# schema.net
KiCad netlist of a schematic drawn in EAGLE
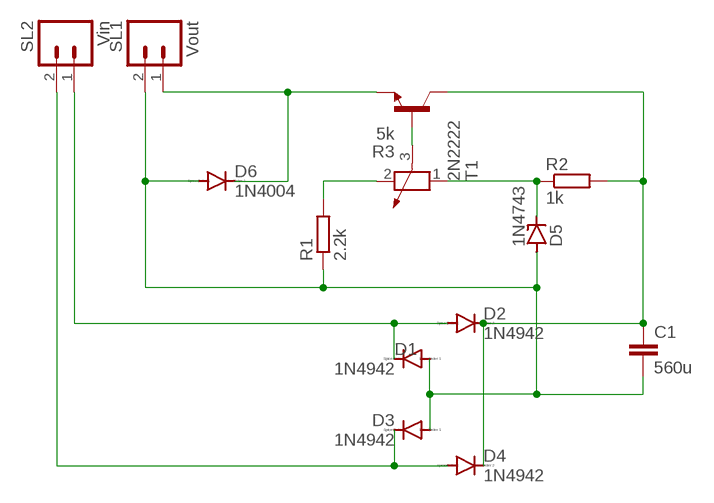
[diagram p0: schematic, sheet 1]

(export (version "E")
  (design (tool "Eeschema 10.0.6"))
  (components
    (comp (ref "C1")
      (value "560u")
      (footprint "eagle-import:C025-025X050")
      (libsource (lib "eagle-import") (part "C-EU025-025X050"))
    )
    (comp (ref "D1")
      (value "1N4942")
      (footprint "eagle-import:DO41-10")
      (libsource (lib "eagle-import") (part "1N4942"))
    )
    (comp (ref "D2")
      (value "1N4942")
      (footprint "eagle-import:DO41-10")
      (libsource (lib "eagle-import") (part "1N4942"))
    )
    (comp (ref "D3")
      (value "1N4942")
      (footprint "eagle-import:DO41-10")
      (libsource (lib "eagle-import") (part "1N4942"))
    )
    (comp (ref "D4")
      (value "1N4942")
      (footprint "eagle-import:DO41-10")
      (libsource (lib "eagle-import") (part "1N4942"))
    )
    (comp (ref "D5")
      (value "1N4743")
      (footprint "eagle-import:DO41Z10")
      (libsource (lib "eagle-import") (part "1N4728"))
    )
    (comp (ref "D6")
      (value "1N4004")
      (footprint "eagle-import:DO41-10")
      (libsource (lib "eagle-import") (part "1N4004"))
    )
    (comp (ref "R1")
      (value "2.2k")
      (footprint "eagle-import:0204_7")
      (libsource (lib "eagle-import") (part "R-EU_0204/7"))
    )
    (comp (ref "R2")
      (value "1k")
      (footprint "eagle-import:0204_7")
      (libsource (lib "eagle-import") (part "R-EU_0204/7"))
    )
    (comp (ref "R3")
      (value "5k")
      (footprint "eagle-import:PT-10")
      (libsource (lib "eagle-import") (part "POTENTIOMETER_PT-10"))
    )
    (comp (ref "SL1")
      (value "Vout")
      (footprint "eagle-import:02P")
      (libsource (lib "eagle-import") (part "M02"))
    )
    (comp (ref "SL2")
      (value "Vin")
      (footprint "eagle-import:02P")
      (libsource (lib "eagle-import") (part "M02"))
    )
    (comp (ref "T1")
      (value "2N2222")
      (footprint "eagle-import:TO18")
      (libsource (lib "eagle-import") (part "2N2222"))
    )
  )
  (nets
    (net (code "1") (name "Net-(C1-Pad2)") (class "Default")
      (node (ref "C1") (pin "2") (pinfunction "2_2") (pintype "passive"))
      (node (ref "D1") (pin "A") (pinfunction "A_A") (pintype "passive"))
      (node (ref "D3") (pin "A") (pinfunction "A_A") (pintype "passive"))
      (node (ref "D5") (pin "A") (pinfunction "A_A") (pintype "passive"))
      (node (ref "D6") (pin "A") (pinfunction "A_A") (pintype "passive"))
      (node (ref "R1") (pin "1") (pinfunction "1_1") (pintype "passive"))
      (node (ref "SL1") (pin "2") (pinfunction "2_2") (pintype "passive"))
    )
    (net (code "2") (name "Net-(D1-PadC)") (class "Default")
      (node (ref "D1") (pin "C") (pinfunction "C_C") (pintype "passive"))
      (node (ref "D2") (pin "A") (pinfunction "A_A") (pintype "passive"))
      (node (ref "SL2") (pin "1") (pinfunction "1_1") (pintype "passive"))
    )
    (net (code "3") (name "Net-(D3-PadC)") (class "Default")
      (node (ref "D3") (pin "C") (pinfunction "C_C") (pintype "passive"))
      (node (ref "D4") (pin "A") (pinfunction "A_A") (pintype "passive"))
      (node (ref "SL2") (pin "2") (pinfunction "2_2") (pintype "passive"))
    )
    (net (code "4") (name "Net-(D5-PadC)") (class "Default")
      (node (ref "D5") (pin "C") (pinfunction "C_C") (pintype "passive"))
      (node (ref "R2") (pin "1") (pinfunction "1_1") (pintype "passive"))
      (node (ref "R3") (pin "1") (pinfunction "1_1") (pintype "passive"))
    )
    (net (code "5") (name "Net-(R1-Pad2)") (class "Default")
      (node (ref "R1") (pin "2") (pinfunction "2_2") (pintype "passive"))
      (node (ref "R3") (pin "2") (pinfunction "2_2") (pintype "passive"))
    )
    (net (code "6") (name "Net-(T1-B)") (class "Default")
      (node (ref "R3") (pin "3") (pinfunction "3_3") (pintype "passive"))
      (node (ref "T1") (pin "2") (pinfunction "B_2") (pintype "passive"))
    )
    (net (code "7") (name "Net-(T1-C)") (class "Default")
      (node (ref "C1") (pin "1") (pinfunction "1_1") (pintype "passive"))
      (node (ref "D2") (pin "C") (pinfunction "C_C") (pintype "passive"))
      (node (ref "D4") (pin "C") (pinfunction "C_C") (pintype "passive"))
      (node (ref "R2") (pin "2") (pinfunction "2_2") (pintype "passive"))
      (node (ref "T1") (pin "3") (pinfunction "C_3") (pintype "passive"))
    )
    (net (code "8") (name "Net-(T1-E)") (class "Default")
      (node (ref "D6") (pin "C") (pinfunction "C_C") (pintype "passive"))
      (node (ref "SL1") (pin "1") (pinfunction "1_1") (pintype "passive"))
      (node (ref "T1") (pin "1") (pinfunction "E_1") (pintype "passive"))
    )
  )
)
